# ADS1299_4_Feather.net
KiCad netlist of a schematic drawn in EAGLE
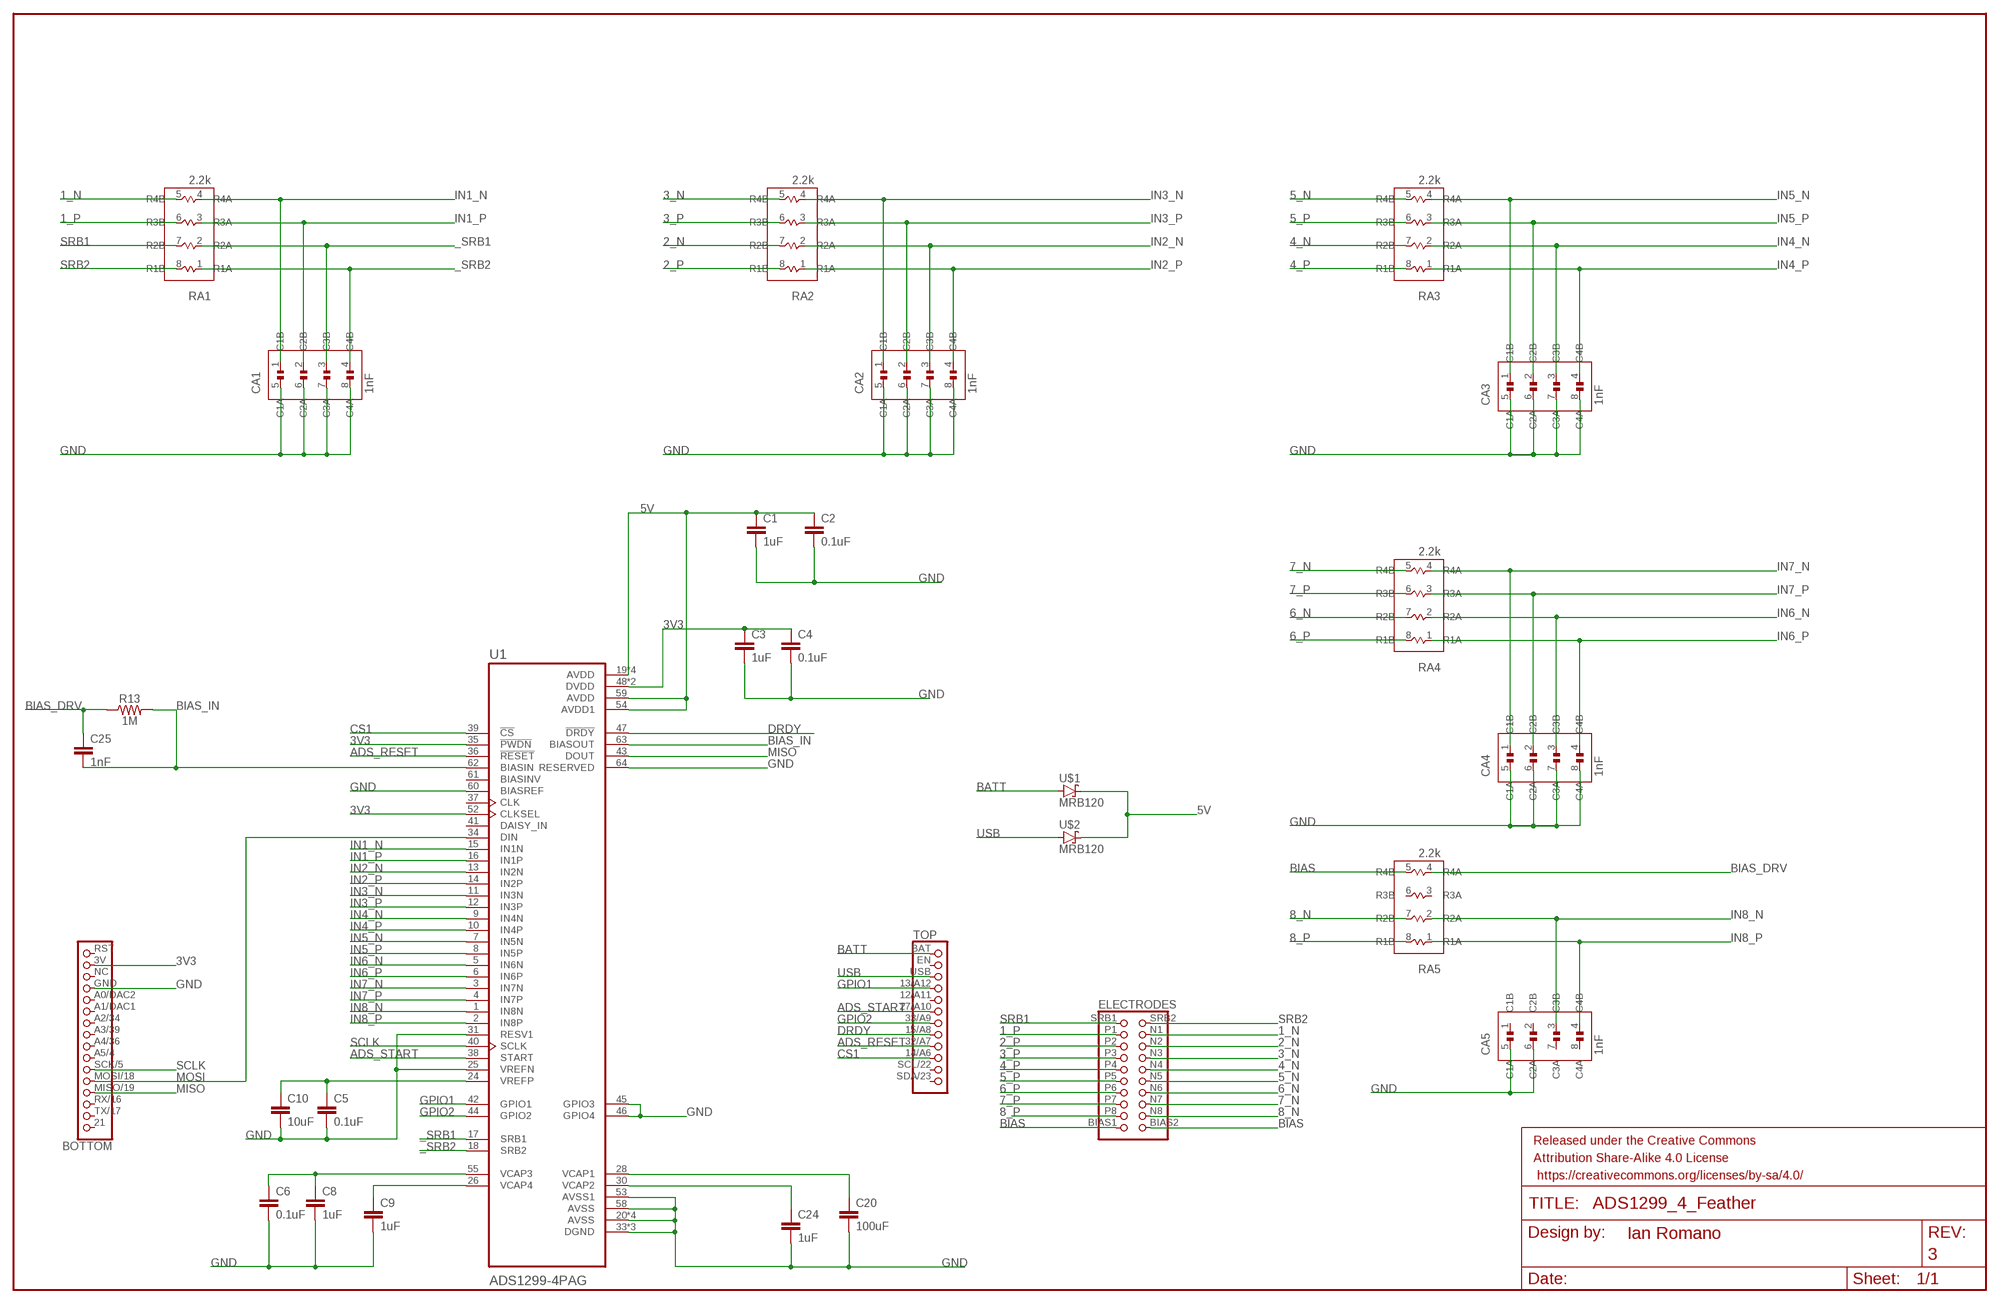
[diagram p0: schematic, sheet 1]

(export (version "E")
  (design (tool "Eeschema 10.0.6"))
  (components
    (comp (ref "BOTTOM")
      (value "MICROBUILDER_HEADER-1X16_76MIL")
      (footprint "eagle-import:MICROBUILDER_1X16_ROUND_76MIL")
      (libsource (lib "eagle-import") (part "MICROBUILDER_HEADER-1X16_76MIL"))
    )
    (comp (ref "C1")
      (value "1uF")
      (footprint "eagle-import:0805")
      (libsource (lib "eagle-import") (part "10UF-0805-10V-10%"))
    )
    (comp (ref "C2")
      (value "0.1uF")
      (footprint "eagle-import:0805")
      (libsource (lib "eagle-import") (part "10UF-0805-10V-10%"))
    )
    (comp (ref "C3")
      (value "1uF")
      (footprint "eagle-import:0805")
      (libsource (lib "eagle-import") (part "10UF-0805-10V-10%"))
    )
    (comp (ref "C4")
      (value "0.1uF")
      (footprint "eagle-import:0805")
      (libsource (lib "eagle-import") (part "10UF-0805-10V-10%"))
    )
    (comp (ref "C5")
      (value "0.1uF")
      (footprint "eagle-import:0805")
      (libsource (lib "eagle-import") (part "10UF-0805-10V-10%"))
    )
    (comp (ref "C6")
      (value "0.1uF")
      (footprint "eagle-import:0805")
      (libsource (lib "eagle-import") (part "10UF-0805-10V-10%"))
    )
    (comp (ref "C8")
      (value "1uF")
      (footprint "eagle-import:0805")
      (libsource (lib "eagle-import") (part "10UF-0805-10V-10%"))
    )
    (comp (ref "C9")
      (value "1uF")
      (footprint "eagle-import:0805")
      (libsource (lib "eagle-import") (part "10UF-0805-10V-10%"))
    )
    (comp (ref "C10")
      (value "10uF")
      (footprint "eagle-import:0805")
      (libsource (lib "eagle-import") (part "10UF-0805-10V-10%"))
    )
    (comp (ref "C20")
      (value "100uF")
      (footprint "eagle-import:0805")
      (libsource (lib "eagle-import") (part "10UF-0805-10V-10%"))
    )
    (comp (ref "C24")
      (value "1uF")
      (footprint "eagle-import:0805")
      (libsource (lib "eagle-import") (part "10UF-0805-10V-10%"))
    )
    (comp (ref "C25")
      (value "1nF")
      (footprint "eagle-import:0805")
      (libsource (lib "eagle-import") (part "10UF-0805-10V-10%"))
    )
    (comp (ref "CA1")
      (value "1nF")
      (footprint "eagle-import:SLEEPSURELIB_CAPCAXE50P210X130X94-8N")
      (libsource (lib "eagle-import") (part "SLEEPSURELIB_W2A45C103MAT2A"))
    )
    (comp (ref "CA2")
      (value "1nF")
      (footprint "eagle-import:SLEEPSURELIB_CAPCAXE50P210X130X94-8N")
      (libsource (lib "eagle-import") (part "SLEEPSURELIB_W2A45C103MAT2A"))
    )
    (comp (ref "CA3")
      (value "1nF")
      (footprint "eagle-import:SLEEPSURELIB_CAPCAXE50P210X130X94-8N")
      (libsource (lib "eagle-import") (part "SLEEPSURELIB_W2A45C103MAT2A"))
    )
    (comp (ref "CA4")
      (value "1nF")
      (footprint "eagle-import:SLEEPSURELIB_CAPCAXE50P210X130X94-8N")
      (libsource (lib "eagle-import") (part "SLEEPSURELIB_W2A45C103MAT2A"))
    )
    (comp (ref "CA5")
      (value "1nF")
      (footprint "eagle-import:SLEEPSURELIB_CAPCAXE50P210X130X94-8N")
      (libsource (lib "eagle-import") (part "SLEEPSURELIB_W2A45C103MAT2A"))
    )
    (comp (ref "ELECTRODES")
      (value "SLEEPSURELIB_PINHD-2X10-BIG")
      (footprint "eagle-import:SLEEPSURELIB_2X10-BIG")
      (libsource (lib "eagle-import") (part "SLEEPSURELIB_PINHD-2X10-BIG"))
    )
    (comp (ref "FRAME1")
      (value "FRAME-LEDGER")
      (footprint "eagle-import:CREATIVE_COMMONS")
      (fields (field (name "DESIGNER") "Ian Romano") (field (name "REV") "3"))
      (libsource (lib "eagle-import") (part "FRAME-LEDGER"))
    )
    (comp (ref "R13")
      (value "1M")
      (footprint "eagle-import:0805")
      (libsource (lib "eagle-import") (part "RESISTOR0805"))
    )
    (comp (ref "RA1")
      (value "2.2k")
      (footprint "eagle-import:SLEEPSURELIB_RESCAXS50P200X100X45-8N")
      (libsource (lib "eagle-import") (part "SLEEPSURELIB_EXB-28V222JX"))
    )
    (comp (ref "RA2")
      (value "2.2k")
      (footprint "eagle-import:SLEEPSURELIB_RESCAXS50P200X100X45-8N")
      (libsource (lib "eagle-import") (part "SLEEPSURELIB_EXB-28V222JX"))
    )
    (comp (ref "RA3")
      (value "2.2k")
      (footprint "eagle-import:SLEEPSURELIB_RESCAXS50P200X100X45-8N")
      (libsource (lib "eagle-import") (part "SLEEPSURELIB_EXB-28V222JX"))
    )
    (comp (ref "RA4")
      (value "2.2k")
      (footprint "eagle-import:SLEEPSURELIB_RESCAXS50P200X100X45-8N")
      (libsource (lib "eagle-import") (part "SLEEPSURELIB_EXB-28V222JX"))
    )
    (comp (ref "RA5")
      (value "2.2k")
      (footprint "eagle-import:SLEEPSURELIB_RESCAXS50P200X100X45-8N")
      (libsource (lib "eagle-import") (part "SLEEPSURELIB_EXB-28V222JX"))
    )
    (comp (ref "TOP")
      (value "MICROBUILDER_HEADER-1X1276MIL")
      (footprint "eagle-import:MICROBUILDER_1X12_ROUND_76MIL")
      (libsource (lib "eagle-import") (part "MICROBUILDER_HEADER-1X1276MIL"))
    )
    (comp (ref "U$1")
      (value "MRB120")
      (footprint "eagle-import:SOD123FL")
      (libsource (lib "eagle-import") (part "MBR160HW"))
    )
    (comp (ref "U$2")
      (value "MRB120")
      (footprint "eagle-import:SOD123FL")
      (libsource (lib "eagle-import") (part "MBR160HW"))
    )
    (comp (ref "U1")
      (value "ADS1299-4PAG")
      (footprint "eagle-import:QFP50P1200X1200X120-64N")
      (fields (field (name "MF") "Texas Instruments"))
      (libsource (lib "eagle-import") (part "ADS1299-4PAG"))
    )
  )
  (nets
    (net (code "1") (name "/1_N") (class "Default")
      (node (ref "ELECTRODES") (pin "N1") (pinfunction "N1_N1") (pintype "passive"))
      (node (ref "RA1") (pin "5") (pinfunction "R4B_5") (pintype "bidirectional"))
    )
    (net (code "2") (name "/1_P") (class "Default")
      (node (ref "ELECTRODES") (pin "P1") (pinfunction "P1_P1") (pintype "passive"))
      (node (ref "RA1") (pin "6") (pinfunction "R3B_6") (pintype "bidirectional"))
    )
    (net (code "3") (name "/2_N") (class "Default")
      (node (ref "ELECTRODES") (pin "N2") (pinfunction "N2_N2") (pintype "passive"))
      (node (ref "RA2") (pin "7") (pinfunction "R2B_7") (pintype "bidirectional"))
    )
    (net (code "4") (name "/2_P") (class "Default")
      (node (ref "ELECTRODES") (pin "P2") (pinfunction "P2_P2") (pintype "passive"))
      (node (ref "RA2") (pin "8") (pinfunction "R1B_8") (pintype "bidirectional"))
    )
    (net (code "5") (name "/3V3") (class "Default")
      (node (ref "BOTTOM") (pin "3V") (pinfunction "3V_3V") (pintype "passive"))
      (node (ref "C3") (pin "1") (pinfunction "1_1") (pintype "passive"))
      (node (ref "C4") (pin "1") (pinfunction "1_1") (pintype "passive"))
      (node (ref "U1") (pin "35") (pinfunction "~{PWDN}_35") (pintype "input"))
      (node (ref "U1") (pin "48") (pinfunction "DVDD_48") (pintype "power_in"))
      (node (ref "U1") (pin "50") (pinfunction "DVDD_50") (pintype "power_in"))
      (node (ref "U1") (pin "52") (pinfunction "CLKSEL_52") (pintype "input"))
    )
    (net (code "6") (name "/3_N") (class "Default")
      (node (ref "ELECTRODES") (pin "N3") (pinfunction "N3_N3") (pintype "passive"))
      (node (ref "RA2") (pin "5") (pinfunction "R4B_5") (pintype "bidirectional"))
    )
    (net (code "7") (name "/3_P") (class "Default")
      (node (ref "ELECTRODES") (pin "P3") (pinfunction "P3_P3") (pintype "passive"))
      (node (ref "RA2") (pin "6") (pinfunction "R3B_6") (pintype "bidirectional"))
    )
    (net (code "8") (name "/4_N") (class "Default")
      (node (ref "ELECTRODES") (pin "N4") (pinfunction "N4_N4") (pintype "passive"))
      (node (ref "RA3") (pin "7") (pinfunction "R2B_7") (pintype "bidirectional"))
    )
    (net (code "9") (name "/4_P") (class "Default")
      (node (ref "ELECTRODES") (pin "P4") (pinfunction "P4_P4") (pintype "passive"))
      (node (ref "RA3") (pin "8") (pinfunction "R1B_8") (pintype "bidirectional"))
    )
    (net (code "10") (name "/5V") (class "Default")
      (node (ref "C1") (pin "1") (pinfunction "1_1") (pintype "passive"))
      (node (ref "C2") (pin "1") (pinfunction "1_1") (pintype "passive"))
      (node (ref "U$1") (pin "C") (pinfunction "C_C") (pintype "passive"))
      (node (ref "U$2") (pin "C") (pinfunction "C_C") (pintype "passive"))
      (node (ref "U1") (pin "19") (pinfunction "AVDD_19") (pintype "power_in"))
      (node (ref "U1") (pin "21") (pinfunction "AVDD_21") (pintype "power_in"))
      (node (ref "U1") (pin "22") (pinfunction "AVDD_22") (pintype "power_in"))
      (node (ref "U1") (pin "54") (pinfunction "AVDD1_54") (pintype "power_in"))
      (node (ref "U1") (pin "56") (pinfunction "AVDD_56") (pintype "power_in"))
      (node (ref "U1") (pin "59") (pinfunction "AVDD_59") (pintype "power_in"))
    )
    (net (code "11") (name "/5_N") (class "Default")
      (node (ref "ELECTRODES") (pin "N5") (pinfunction "N5_N5") (pintype "passive"))
      (node (ref "RA3") (pin "5") (pinfunction "R4B_5") (pintype "bidirectional"))
    )
    (net (code "12") (name "/5_P") (class "Default")
      (node (ref "ELECTRODES") (pin "P5") (pinfunction "P5_P5") (pintype "passive"))
      (node (ref "RA3") (pin "6") (pinfunction "R3B_6") (pintype "bidirectional"))
    )
    (net (code "13") (name "/6_N") (class "Default")
      (node (ref "ELECTRODES") (pin "N6") (pinfunction "N6_N6") (pintype "passive"))
      (node (ref "RA4") (pin "7") (pinfunction "R2B_7") (pintype "bidirectional"))
    )
    (net (code "14") (name "/6_P") (class "Default")
      (node (ref "ELECTRODES") (pin "P6") (pinfunction "P6_P6") (pintype "passive"))
      (node (ref "RA4") (pin "8") (pinfunction "R1B_8") (pintype "bidirectional"))
    )
    (net (code "15") (name "/7_N") (class "Default")
      (node (ref "ELECTRODES") (pin "N7") (pinfunction "N7_N7") (pintype "passive"))
      (node (ref "RA4") (pin "5") (pinfunction "R4B_5") (pintype "bidirectional"))
    )
    (net (code "16") (name "/7_P") (class "Default")
      (node (ref "ELECTRODES") (pin "P7") (pinfunction "P7_P7") (pintype "passive"))
      (node (ref "RA4") (pin "6") (pinfunction "R3B_6") (pintype "bidirectional"))
    )
    (net (code "17") (name "/8_N") (class "Default")
      (node (ref "ELECTRODES") (pin "N8") (pinfunction "N8_N8") (pintype "passive"))
      (node (ref "RA5") (pin "7") (pinfunction "R2B_7") (pintype "bidirectional"))
    )
    (net (code "18") (name "/8_P") (class "Default")
      (node (ref "ELECTRODES") (pin "P8") (pinfunction "P8_P8") (pintype "passive"))
      (node (ref "RA5") (pin "8") (pinfunction "R1B_8") (pintype "bidirectional"))
    )
    (net (code "19") (name "/ADS_RESET") (class "Default")
      (node (ref "TOP") (pin "32/A7") (pinfunction "32_32/A7") (pintype "passive"))
      (node (ref "U1") (pin "36") (pinfunction "~{RESET}_36") (pintype "input"))
    )
    (net (code "20") (name "/ADS_START") (class "Default")
      (node (ref "TOP") (pin "27/A10") (pinfunction "27_27/A10") (pintype "passive"))
      (node (ref "U1") (pin "38") (pinfunction "START_38") (pintype "input"))
    )
    (net (code "21") (name "/BATT") (class "Default")
      (node (ref "TOP") (pin "BAT") (pinfunction "BAT_BAT") (pintype "passive"))
      (node (ref "U$1") (pin "A") (pinfunction "A_A") (pintype "passive"))
    )
    (net (code "22") (name "/BIAS") (class "Default")
      (node (ref "ELECTRODES") (pin "BIAS1") (pinfunction "BIAS1_BIAS1") (pintype "passive"))
      (node (ref "ELECTRODES") (pin "BIAS2") (pinfunction "BIAS2_BIAS2") (pintype "passive"))
      (node (ref "RA5") (pin "5") (pinfunction "R4B_5") (pintype "bidirectional"))
    )
    (net (code "23") (name "/BIAS_DRV") (class "Default")
      (node (ref "C25") (pin "1") (pinfunction "1_1") (pintype "passive"))
      (node (ref "R13") (pin "1") (pinfunction "1_1") (pintype "passive"))
      (node (ref "RA5") (pin "4") (pinfunction "R4A_4") (pintype "bidirectional"))
    )
    (net (code "24") (name "/BIAS_IN") (class "Default")
      (node (ref "C25") (pin "2") (pinfunction "2_2") (pintype "passive"))
      (node (ref "R13") (pin "2") (pinfunction "2_2") (pintype "passive"))
      (node (ref "U1") (pin "62") (pinfunction "BIASIN_62") (pintype "input"))
      (node (ref "U1") (pin "63") (pinfunction "BIASOUT_63") (pintype "output"))
    )
    (net (code "25") (name "/CS1") (class "Default")
      (node (ref "TOP") (pin "14/A6") (pinfunction "14_14/A6") (pintype "passive"))
      (node (ref "U1") (pin "39") (pinfunction "~{CS}_39") (pintype "input"))
    )
    (net (code "26") (name "/DRDY") (class "Default")
      (node (ref "TOP") (pin "15/A8") (pinfunction "15_15/A8") (pintype "passive"))
      (node (ref "U1") (pin "47") (pinfunction "~{DRDY}_47") (pintype "output"))
    )
    (net (code "27") (name "/GND") (class "Default")
      (node (ref "BOTTOM") (pin "GND") (pinfunction "GND_GND") (pintype "passive"))
      (node (ref "C1") (pin "2") (pinfunction "2_2") (pintype "passive"))
      (node (ref "C10") (pin "2") (pinfunction "2_2") (pintype "passive"))
      (node (ref "C2") (pin "2") (pinfunction "2_2") (pintype "passive"))
      (node (ref "C20") (pin "2") (pinfunction "2_2") (pintype "passive"))
      (node (ref "C24") (pin "2") (pinfunction "2_2") (pintype "passive"))
      (node (ref "C3") (pin "2") (pinfunction "2_2") (pintype "passive"))
      (node (ref "C4") (pin "2") (pinfunction "2_2") (pintype "passive"))
      (node (ref "C5") (pin "2") (pinfunction "2_2") (pintype "passive"))
      (node (ref "C6") (pin "2") (pinfunction "2_2") (pintype "passive"))
      (node (ref "C8") (pin "2") (pinfunction "2_2") (pintype "passive"))
      (node (ref "C9") (pin "2") (pinfunction "2_2") (pintype "passive"))
      (node (ref "CA1") (pin "5") (pinfunction "C1A_5") (pintype "bidirectional"))
      (node (ref "CA1") (pin "6") (pinfunction "C2A_6") (pintype "bidirectional"))
      (node (ref "CA1") (pin "7") (pinfunction "C3A_7") (pintype "bidirectional"))
      (node (ref "CA1") (pin "8") (pinfunction "C4A_8") (pintype "bidirectional"))
      (node (ref "CA2") (pin "5") (pinfunction "C1A_5") (pintype "bidirectional"))
      (node (ref "CA2") (pin "6") (pinfunction "C2A_6") (pintype "bidirectional"))
      (node (ref "CA2") (pin "7") (pinfunction "C3A_7") (pintype "bidirectional"))
      (node (ref "CA2") (pin "8") (pinfunction "C4A_8") (pintype "bidirectional"))
      (node (ref "CA3") (pin "5") (pinfunction "C1A_5") (pintype "bidirectional"))
      (node (ref "CA3") (pin "6") (pinfunction "C2A_6") (pintype "bidirectional"))
      (node (ref "CA3") (pin "7") (pinfunction "C3A_7") (pintype "bidirectional"))
      (node (ref "CA3") (pin "8") (pinfunction "C4A_8") (pintype "bidirectional"))
      (node (ref "CA4") (pin "5") (pinfunction "C1A_5") (pintype "bidirectional"))
      (node (ref "CA4") (pin "6") (pinfunction "C2A_6") (pintype "bidirectional"))
      (node (ref "CA4") (pin "7") (pinfunction "C3A_7") (pintype "bidirectional"))
      (node (ref "CA4") (pin "8") (pinfunction "C4A_8") (pintype "bidirectional"))
      (node (ref "CA5") (pin "5") (pinfunction "C1A_5") (pintype "bidirectional"))
      (node (ref "CA5") (pin "6") (pinfunction "C2A_6") (pintype "bidirectional"))
      (node (ref "U1") (pin "20") (pinfunction "AVSS_20") (pintype "power_in"))
      (node (ref "U1") (pin "23") (pinfunction "AVSS_23") (pintype "power_in"))
      (node (ref "U1") (pin "25") (pinfunction "VREFN_25") (pintype "input"))
      (node (ref "U1") (pin "31") (pinfunction "RESV1_31") (pintype "input"))
      (node (ref "U1") (pin "32") (pinfunction "AVSS_32") (pintype "power_in"))
      (node (ref "U1") (pin "33") (pinfunction "DGND_33") (pintype "power_in"))
      (node (ref "U1") (pin "45") (pinfunction "GPIO3_45") (pintype "bidirectional"))
      (node (ref "U1") (pin "46") (pinfunction "GPIO4_46") (pintype "bidirectional"))
      (node (ref "U1") (pin "49") (pinfunction "DGND_49") (pintype "power_in"))
      (node (ref "U1") (pin "51") (pinfunction "DGND_51") (pintype "power_in"))
      (node (ref "U1") (pin "53") (pinfunction "AVSS1_53") (pintype "power_in"))
      (node (ref "U1") (pin "57") (pinfunction "AVSS_57") (pintype "power_in"))
      (node (ref "U1") (pin "58") (pinfunction "AVSS_58") (pintype "power_in"))
      (node (ref "U1") (pin "60") (pinfunction "BIASREF_60") (pintype "input"))
      (node (ref "U1") (pin "64") (pinfunction "RESERVED_64") (pintype "output"))
    )
    (net (code "28") (name "/GPIO1") (class "Default")
      (node (ref "TOP") (pin "13/A12") (pinfunction "13_13/A12") (pintype "passive"))
      (node (ref "U1") (pin "42") (pinfunction "GPIO1_42") (pintype "bidirectional"))
    )
    (net (code "29") (name "/GPIO2") (class "Default")
      (node (ref "TOP") (pin "33/A9") (pinfunction "33_33/A9") (pintype "passive"))
      (node (ref "U1") (pin "44") (pinfunction "GPIO2_44") (pintype "bidirectional"))
    )
    (net (code "30") (name "/IN1_N") (class "Default")
      (node (ref "CA1") (pin "1") (pinfunction "C1B_1") (pintype "bidirectional"))
      (node (ref "RA1") (pin "4") (pinfunction "R4A_4") (pintype "bidirectional"))
      (node (ref "U1") (pin "15") (pinfunction "IN1N_15") (pintype "input"))
    )
    (net (code "31") (name "/IN1_P") (class "Default")
      (node (ref "CA1") (pin "2") (pinfunction "C2B_2") (pintype "bidirectional"))
      (node (ref "RA1") (pin "3") (pinfunction "R3A_3") (pintype "bidirectional"))
      (node (ref "U1") (pin "16") (pinfunction "IN1P_16") (pintype "input"))
    )
    (net (code "32") (name "/IN2_N") (class "Default")
      (node (ref "CA2") (pin "3") (pinfunction "C3B_3") (pintype "bidirectional"))
      (node (ref "RA2") (pin "2") (pinfunction "R2A_2") (pintype "bidirectional"))
      (node (ref "U1") (pin "13") (pinfunction "IN2N_13") (pintype "input"))
    )
    (net (code "33") (name "/IN2_P") (class "Default")
      (node (ref "CA2") (pin "4") (pinfunction "C4B_4") (pintype "bidirectional"))
      (node (ref "RA2") (pin "1") (pinfunction "R1A_1") (pintype "bidirectional"))
      (node (ref "U1") (pin "14") (pinfunction "IN2P_14") (pintype "input"))
    )
    (net (code "34") (name "/IN3_N") (class "Default")
      (node (ref "CA2") (pin "1") (pinfunction "C1B_1") (pintype "bidirectional"))
      (node (ref "RA2") (pin "4") (pinfunction "R4A_4") (pintype "bidirectional"))
      (node (ref "U1") (pin "11") (pinfunction "IN3N_11") (pintype "input"))
    )
    (net (code "35") (name "/IN3_P") (class "Default")
      (node (ref "CA2") (pin "2") (pinfunction "C2B_2") (pintype "bidirectional"))
      (node (ref "RA2") (pin "3") (pinfunction "R3A_3") (pintype "bidirectional"))
      (node (ref "U1") (pin "12") (pinfunction "IN3P_12") (pintype "input"))
    )
    (net (code "36") (name "/IN4_N") (class "Default")
      (node (ref "CA3") (pin "3") (pinfunction "C3B_3") (pintype "bidirectional"))
      (node (ref "RA3") (pin "2") (pinfunction "R2A_2") (pintype "bidirectional"))
      (node (ref "U1") (pin "9") (pinfunction "IN4N_9") (pintype "input"))
    )
    (net (code "37") (name "/IN4_P") (class "Default")
      (node (ref "CA3") (pin "4") (pinfunction "C4B_4") (pintype "bidirectional"))
      (node (ref "RA3") (pin "1") (pinfunction "R1A_1") (pintype "bidirectional"))
      (node (ref "U1") (pin "10") (pinfunction "IN4P_10") (pintype "input"))
    )
    (net (code "38") (name "/IN5_N") (class "Default")
      (node (ref "CA3") (pin "1") (pinfunction "C1B_1") (pintype "bidirectional"))
      (node (ref "RA3") (pin "4") (pinfunction "R4A_4") (pintype "bidirectional"))
      (node (ref "U1") (pin "7") (pinfunction "IN5N_7") (pintype "input"))
    )
    (net (code "39") (name "/IN5_P") (class "Default")
      (node (ref "CA3") (pin "2") (pinfunction "C2B_2") (pintype "bidirectional"))
      (node (ref "RA3") (pin "3") (pinfunction "R3A_3") (pintype "bidirectional"))
      (node (ref "U1") (pin "8") (pinfunction "IN5P_8") (pintype "input"))
    )
    (net (code "40") (name "/IN6_N") (class "Default")
      (node (ref "CA4") (pin "3") (pinfunction "C3B_3") (pintype "bidirectional"))
      (node (ref "RA4") (pin "2") (pinfunction "R2A_2") (pintype "bidirectional"))
      (node (ref "U1") (pin "5") (pinfunction "IN6N_5") (pintype "input"))
    )
    (net (code "41") (name "/IN6_P") (class "Default")
      (node (ref "CA4") (pin "4") (pinfunction "C4B_4") (pintype "bidirectional"))
      (node (ref "RA4") (pin "1") (pinfunction "R1A_1") (pintype "bidirectional"))
      (node (ref "U1") (pin "6") (pinfunction "IN6P_6") (pintype "input"))
    )
    (net (code "42") (name "/IN7_N") (class "Default")
      (node (ref "CA4") (pin "1") (pinfunction "C1B_1") (pintype "bidirectional"))
      (node (ref "RA4") (pin "4") (pinfunction "R4A_4") (pintype "bidirectional"))
      (node (ref "U1") (pin "3") (pinfunction "IN7N_3") (pintype "input"))
    )
    (net (code "43") (name "/IN7_P") (class "Default")
      (node (ref "CA4") (pin "2") (pinfunction "C2B_2") (pintype "bidirectional"))
      (node (ref "RA4") (pin "3") (pinfunction "R3A_3") (pintype "bidirectional"))
      (node (ref "U1") (pin "4") (pinfunction "IN7P_4") (pintype "input"))
    )
    (net (code "44") (name "/IN8_N") (class "Default")
      (node (ref "CA5") (pin "3") (pinfunction "C3B_3") (pintype "bidirectional"))
      (node (ref "RA5") (pin "2") (pinfunction "R2A_2") (pintype "bidirectional"))
      (node (ref "U1") (pin "1") (pinfunction "IN8N_1") (pintype "input"))
    )
    (net (code "45") (name "/IN8_P") (class "Default")
      (node (ref "CA5") (pin "4") (pinfunction "C4B_4") (pintype "bidirectional"))
      (node (ref "RA5") (pin "1") (pinfunction "R1A_1") (pintype "bidirectional"))
      (node (ref "U1") (pin "2") (pinfunction "IN8P_2") (pintype "input"))
    )
    (net (code "46") (name "/MISO") (class "Default")
      (node (ref "BOTTOM") (pin "MISO/19") (pinfunction "MISO_MISO/19") (pintype "passive"))
      (node (ref "U1") (pin "43") (pinfunction "DOUT_43") (pintype "output"))
    )
    (net (code "47") (name "/MOSI") (class "Default")
      (node (ref "BOTTOM") (pin "MOSI/18") (pinfunction "MOSI_MOSI/18") (pintype "passive"))
      (node (ref "U1") (pin "34") (pinfunction "DIN_34") (pintype "input"))
    )
    (net (code "48") (name "/SCLK") (class "Default")
      (node (ref "BOTTOM") (pin "SCK/5") (pinfunction "SCK_SCK/5") (pintype "passive"))
      (node (ref "U1") (pin "40") (pinfunction "SCLK_40") (pintype "input"))
    )
    (net (code "49") (name "/SRB1") (class "Default")
      (node (ref "ELECTRODES") (pin "SRB1") (pinfunction "SRB1_SRB1") (pintype "passive"))
      (node (ref "RA1") (pin "7") (pinfunction "R2B_7") (pintype "bidirectional"))
    )
    (net (code "50") (name "/SRB2") (class "Default")
      (node (ref "ELECTRODES") (pin "SRB2") (pinfunction "SRB2_SRB2") (pintype "passive"))
      (node (ref "RA1") (pin "8") (pinfunction "R1B_8") (pintype "bidirectional"))
    )
    (net (code "51") (name "/USB") (class "Default")
      (node (ref "TOP") (pin "USB") (pinfunction "USB_USB") (pintype "passive"))
      (node (ref "U$2") (pin "A") (pinfunction "A_A") (pintype "passive"))
    )
    (net (code "52") (name "/_SRB1") (class "Default")
      (node (ref "CA1") (pin "3") (pinfunction "C3B_3") (pintype "bidirectional"))
      (node (ref "RA1") (pin "2") (pinfunction "R2A_2") (pintype "bidirectional"))
      (node (ref "U1") (pin "17") (pinfunction "SRB1_17") (pintype "bidirectional"))
    )
    (net (code "53") (name "/_SRB2") (class "Default")
      (node (ref "CA1") (pin "4") (pinfunction "C4B_4") (pintype "bidirectional"))
      (node (ref "RA1") (pin "1") (pinfunction "R1A_1") (pintype "bidirectional"))
      (node (ref "U1") (pin "18") (pinfunction "SRB2_18") (pintype "bidirectional"))
    )
    (net (code "54") (name "Net-(U1-VCAP1)") (class "Default")
      (node (ref "C20") (pin "1") (pinfunction "1_1") (pintype "passive"))
      (node (ref "U1") (pin "28") (pinfunction "VCAP1_28") (pintype "output"))
    )
    (net (code "55") (name "Net-(U1-VCAP2)") (class "Default")
      (node (ref "C24") (pin "1") (pinfunction "1_1") (pintype "passive"))
      (node (ref "U1") (pin "30") (pinfunction "VCAP2_30") (pintype "output"))
    )
    (net (code "56") (name "Net-(U1-VCAP3)") (class "Default")
      (node (ref "C6") (pin "1") (pinfunction "1_1") (pintype "passive"))
      (node (ref "C8") (pin "1") (pinfunction "1_1") (pintype "passive"))
      (node (ref "U1") (pin "55") (pinfunction "VCAP3_55") (pintype "bidirectional"))
    )
    (net (code "57") (name "Net-(U1-VCAP4)") (class "Default")
      (node (ref "C9") (pin "1") (pinfunction "1_1") (pintype "passive"))
      (node (ref "U1") (pin "26") (pinfunction "VCAP4_26") (pintype "bidirectional"))
    )
    (net (code "58") (name "Net-(U1-VREFP)") (class "Default")
      (node (ref "C10") (pin "1") (pinfunction "1_1") (pintype "passive"))
      (node (ref "C5") (pin "1") (pinfunction "1_1") (pintype "passive"))
      (node (ref "U1") (pin "24") (pinfunction "VREFP_24") (pintype "input"))
    )
    (net (code "59") (name "unconnected-(BOTTOM-A0-PadA0{slash}DAC2)") (class "Default")
      (node (ref "BOTTOM") (pin "A0/DAC2") (pinfunction "A0_A0/DAC2") (pintype "passive"))
    )
    (net (code "60") (name "unconnected-(BOTTOM-A1-PadA1{slash}DAC1)") (class "Default")
      (node (ref "BOTTOM") (pin "A1/DAC1") (pinfunction "A1_A1/DAC1") (pintype "passive"))
    )
    (net (code "61") (name "unconnected-(BOTTOM-A2-PadA2{slash}34)") (class "Default")
      (node (ref "BOTTOM") (pin "A2/34") (pinfunction "A2_A2/34") (pintype "passive"))
    )
    (net (code "62") (name "unconnected-(BOTTOM-A3-PadA3{slash}39)") (class "Default")
      (node (ref "BOTTOM") (pin "A3/39") (pinfunction "A3_A3/39") (pintype "passive"))
    )
    (net (code "63") (name "unconnected-(BOTTOM-A4-PadA4{slash}36)") (class "Default")
      (node (ref "BOTTOM") (pin "A4/36") (pinfunction "A4_A4/36") (pintype "passive"))
    )
    (net (code "64") (name "unconnected-(BOTTOM-A5-PadA5{slash}4)") (class "Default")
      (node (ref "BOTTOM") (pin "A5/4") (pinfunction "A5_A5/4") (pintype "passive"))
    )
    (net (code "65") (name "unconnected-(BOTTOM-Pad21)") (class "Default")
      (node (ref "BOTTOM") (pin "21") (pinfunction "21_21") (pintype "passive"))
    )
    (net (code "66") (name "unconnected-(BOTTOM-PadNC)") (class "Default")
      (node (ref "BOTTOM") (pin "NC") (pinfunction "NC_NC") (pintype "passive"))
    )
    (net (code "67") (name "unconnected-(BOTTOM-PadRST)") (class "Default")
      (node (ref "BOTTOM") (pin "RST") (pinfunction "RST_RST") (pintype "passive"))
    )
    (net (code "68") (name "unconnected-(BOTTOM-RX-PadRX{slash}16)") (class "Default")
      (node (ref "BOTTOM") (pin "RX/16") (pinfunction "RX_RX/16") (pintype "passive"))
    )
    (net (code "69") (name "unconnected-(BOTTOM-TX-PadTX{slash}17)") (class "Default")
      (node (ref "BOTTOM") (pin "TX/17") (pinfunction "TX_TX/17") (pintype "passive"))
    )
    (net (code "70") (name "unconnected-(CA5-C1B-Pad1)") (class "Default")
      (node (ref "CA5") (pin "1") (pinfunction "C1B_1") (pintype "bidirectional"))
    )
    (net (code "71") (name "unconnected-(CA5-C2B-Pad2)") (class "Default")
      (node (ref "CA5") (pin "2") (pinfunction "C2B_2") (pintype "bidirectional"))
    )
    (net (code "72") (name "unconnected-(CA5-C3A-Pad7)") (class "Default")
      (node (ref "CA5") (pin "7") (pinfunction "C3A_7") (pintype "bidirectional"))
    )
    (net (code "73") (name "unconnected-(CA5-C4A-Pad8)") (class "Default")
      (node (ref "CA5") (pin "8") (pinfunction "C4A_8") (pintype "bidirectional"))
    )
    (net (code "74") (name "unconnected-(RA5-R3A-Pad3)") (class "Default")
      (node (ref "RA5") (pin "3") (pinfunction "R3A_3") (pintype "bidirectional"))
    )
    (net (code "75") (name "unconnected-(RA5-R3B-Pad6)") (class "Default")
      (node (ref "RA5") (pin "6") (pinfunction "R3B_6") (pintype "bidirectional"))
    )
    (net (code "76") (name "unconnected-(TOP-12-Pad12{slash}A11)") (class "Default")
      (node (ref "TOP") (pin "12/A11") (pinfunction "12_12/A11") (pintype "passive"))
    )
    (net (code "77") (name "unconnected-(TOP-PadEN)") (class "Default")
      (node (ref "TOP") (pin "EN") (pinfunction "EN_EN") (pintype "passive"))
    )
    (net (code "78") (name "unconnected-(TOP-SCL-PadSCL{slash}22)") (class "Default")
      (node (ref "TOP") (pin "SCL/22") (pinfunction "SCL_SCL/22") (pintype "passive"))
    )
    (net (code "79") (name "unconnected-(TOP-SDA-PadSDA{slash}23)") (class "Default")
      (node (ref "TOP") (pin "SDA/23") (pinfunction "SDA_SDA/23") (pintype "passive"))
    )
    (net (code "80") (name "unconnected-(U1-BIASINV-Pad61)") (class "Default")
      (node (ref "U1") (pin "61") (pinfunction "BIASINV_61") (pintype "input"))
    )
    (net (code "81") (name "unconnected-(U1-CLK-Pad37)") (class "Default")
      (node (ref "U1") (pin "37") (pinfunction "CLK_37") (pintype "input"))
    )
    (net (code "82") (name "unconnected-(U1-DAISY_IN-Pad41)") (class "Default")
      (node (ref "U1") (pin "41") (pinfunction "DAISY_IN_41") (pintype "input"))
    )
  )
)
